# SOC_SOUND.net
KiCad netlist of a schematic drawn in Altium Designer
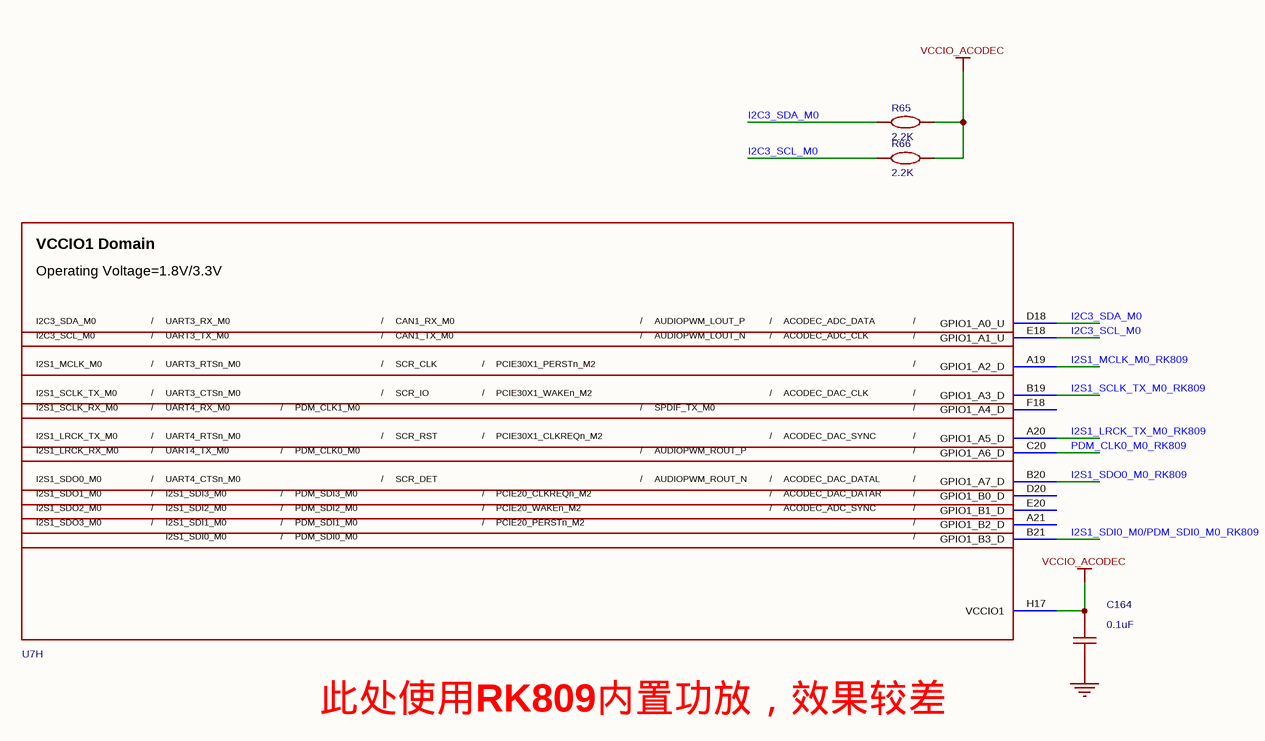
[diagram p0: SOC_SOUND.schdoc]

(export (version "E")
  (design (tool "Eeschema 10.0.6"))
  (components
    (comp (ref "C164")
      (value "0.1uF")
      (footprint "C0201")
      (description "容值:4.7uF;精度:±20%;额定电压:6.3V;温度系数:X5R;")
      (fields
        (field (name "MANUFACTURER") "muRata(村田)")
        (field (name "MANUFACTURERPART") "GRM035R60J475ME15D")
      )
      (libsource (lib "altium-import") (part "root_0_GRM035R60J475ME15D_"))
    )
    (comp (ref "R65")
      (value "2.2K")
      (footprint "R0402")
      (libsource (lib "altium-import") (part "root_0_Res_0402_"))
    )
    (comp (ref "R66")
      (value "2.2K")
      (footprint "R0402")
      (libsource (lib "altium-import") (part "root_0_Res_0402_"))
    )
    (comp (ref "U7")
      (value "RK3568")
      (footprint "BGA-636_L19.0-W19.0-P0.65-BL")
      (libsource (lib "altium-import") (part "root_0_RK3568_"))
    )
  )
  (nets
    (net (code "1") (name "/I2C3_SCL_M0") (class "Default")
      (node (ref "R66") (pin "1") (pinfunction "1_1") (pintype "passive"))
      (node (ref "U7") (pin "E18") (pinfunction "GPIO1_A1_U_E18") (pintype "passive"))
    )
    (net (code "2") (name "/I2C3_SDA_M0") (class "Default")
      (node (ref "R65") (pin "1") (pinfunction "1_1") (pintype "passive"))
      (node (ref "U7") (pin "D18") (pinfunction "GPIO1_A0_U_D18") (pintype "passive"))
    )
    (net (code "3") (name "/I2S1_LRCK_TX_M0_RK809") (class "Default")
      (node (ref "U7") (pin "A20") (pinfunction "GPIO1_A5_D_A20") (pintype "passive"))
    )
    (net (code "4") (name "/I2S1_MCLK_M0_RK809") (class "Default")
      (node (ref "U7") (pin "A19") (pinfunction "GPIO1_A2_D_A19") (pintype "passive"))
    )
    (net (code "5") (name "/I2S1_SCLK_TX_M0_RK809") (class "Default")
      (node (ref "U7") (pin "B19") (pinfunction "GPIO1_A3_D_B19") (pintype "passive"))
    )
    (net (code "6") (name "/I2S1_SDI0_M0{slash}PDM_SDI0_M0_RK809") (class "Default")
      (node (ref "U7") (pin "B21") (pinfunction "GPIO1_B3_D_B21") (pintype "passive"))
    )
    (net (code "7") (name "/I2S1_SDO0_M0_RK809") (class "Default")
      (node (ref "U7") (pin "B20") (pinfunction "GPIO1_A7_D_B20") (pintype "passive"))
    )
    (net (code "8") (name "/PDM_CLK0_M0_RK809") (class "Default")
      (node (ref "U7") (pin "C20") (pinfunction "GPIO1_A6_D_C20") (pintype "passive"))
    )
    (net (code "9") (name "GND") (class "Default")
      (node (ref "C164") (pin "1") (pinfunction "1_1") (pintype "passive"))
    )
    (net (code "10") (name "VCCIO_ACODEC") (class "Default")
      (node (ref "C164") (pin "2") (pinfunction "2_2") (pintype "passive"))
      (node (ref "R65") (pin "2") (pinfunction "2_2") (pintype "passive"))
      (node (ref "R66") (pin "2") (pinfunction "2_2") (pintype "passive"))
      (node (ref "U7") (pin "H17") (pinfunction "VCCIO1_H17") (pintype "passive"))
    )
    (net (code "11") (name "unconnected-(U7H-GPIO1_A4_D-PadF18)") (class "Default")
      (node (ref "U7") (pin "F18") (pinfunction "GPIO1_A4_D_F18") (pintype "passive"))
    )
    (net (code "12") (name "unconnected-(U7H-GPIO1_B0_D-PadD20)") (class "Default")
      (node (ref "U7") (pin "D20") (pinfunction "GPIO1_B0_D_D20") (pintype "passive"))
    )
    (net (code "13") (name "unconnected-(U7H-GPIO1_B1_D-PadE20)") (class "Default")
      (node (ref "U7") (pin "E20") (pinfunction "GPIO1_B1_D_E20") (pintype "passive"))
    )
    (net (code "14") (name "unconnected-(U7H-GPIO1_B2_D-PadA21)") (class "Default")
      (node (ref "U7") (pin "A21") (pinfunction "GPIO1_B2_D_A21") (pintype "passive"))
    )
  )
)
